# AD_1_V1_01.net
KiCad netlist of a schematic drawn in Altium Designer
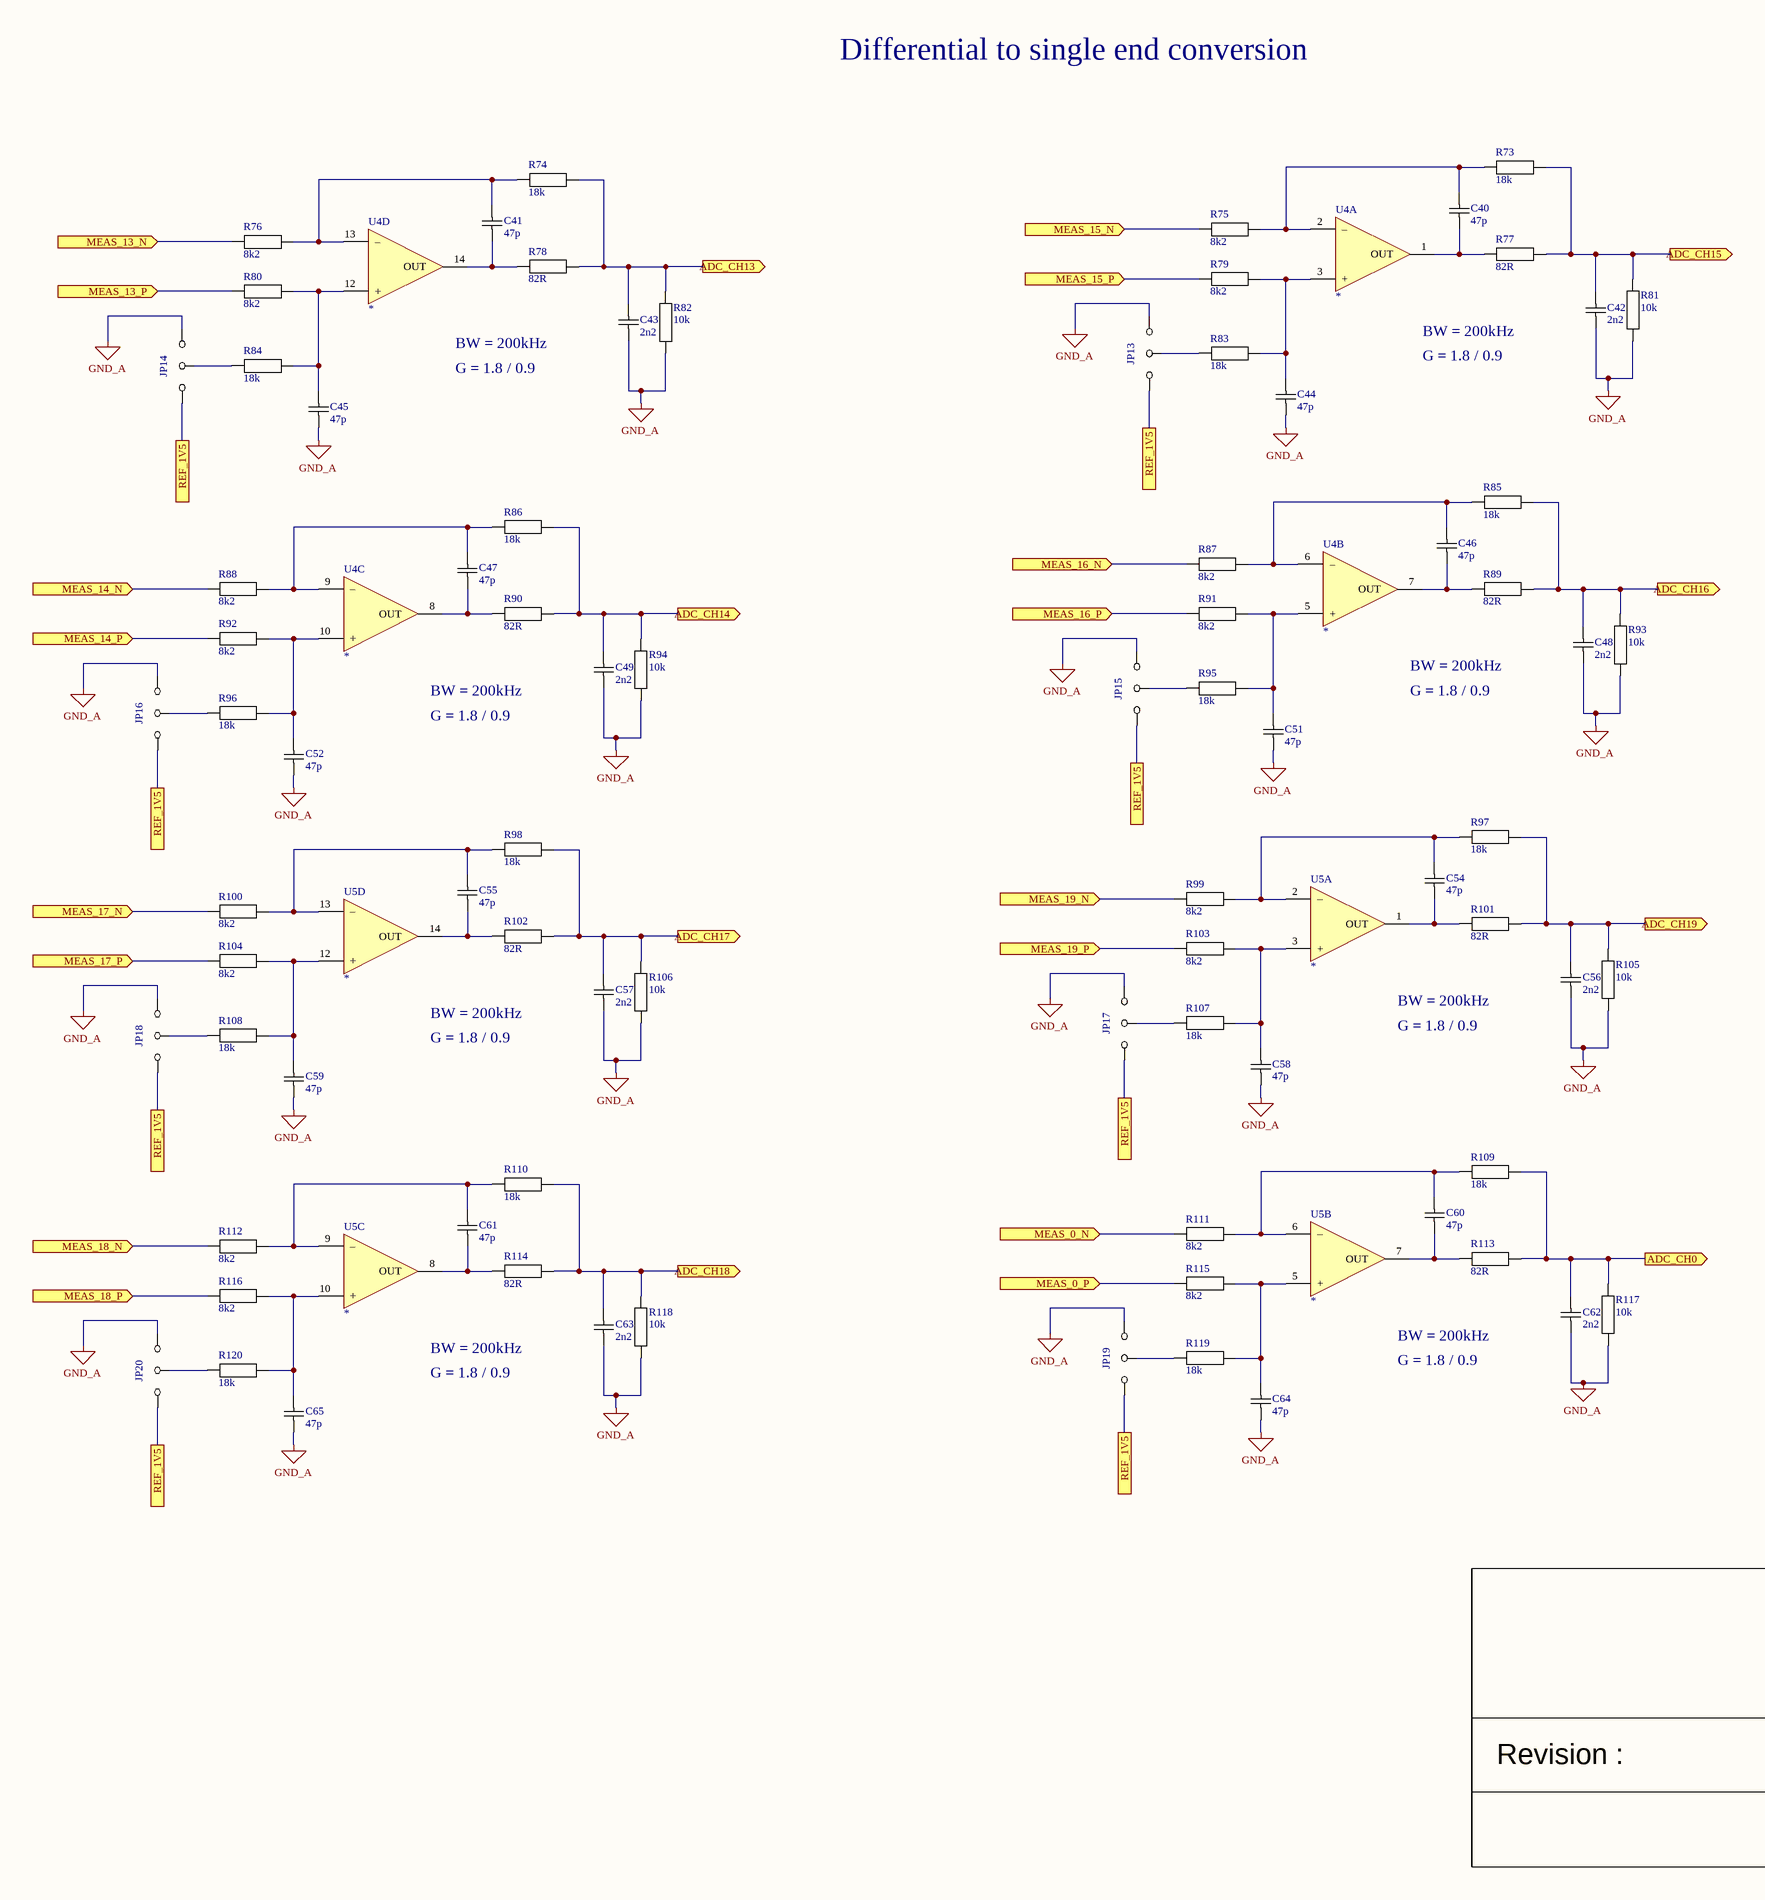
[diagram p0: AD_1_V1_01.SchDoc, left]
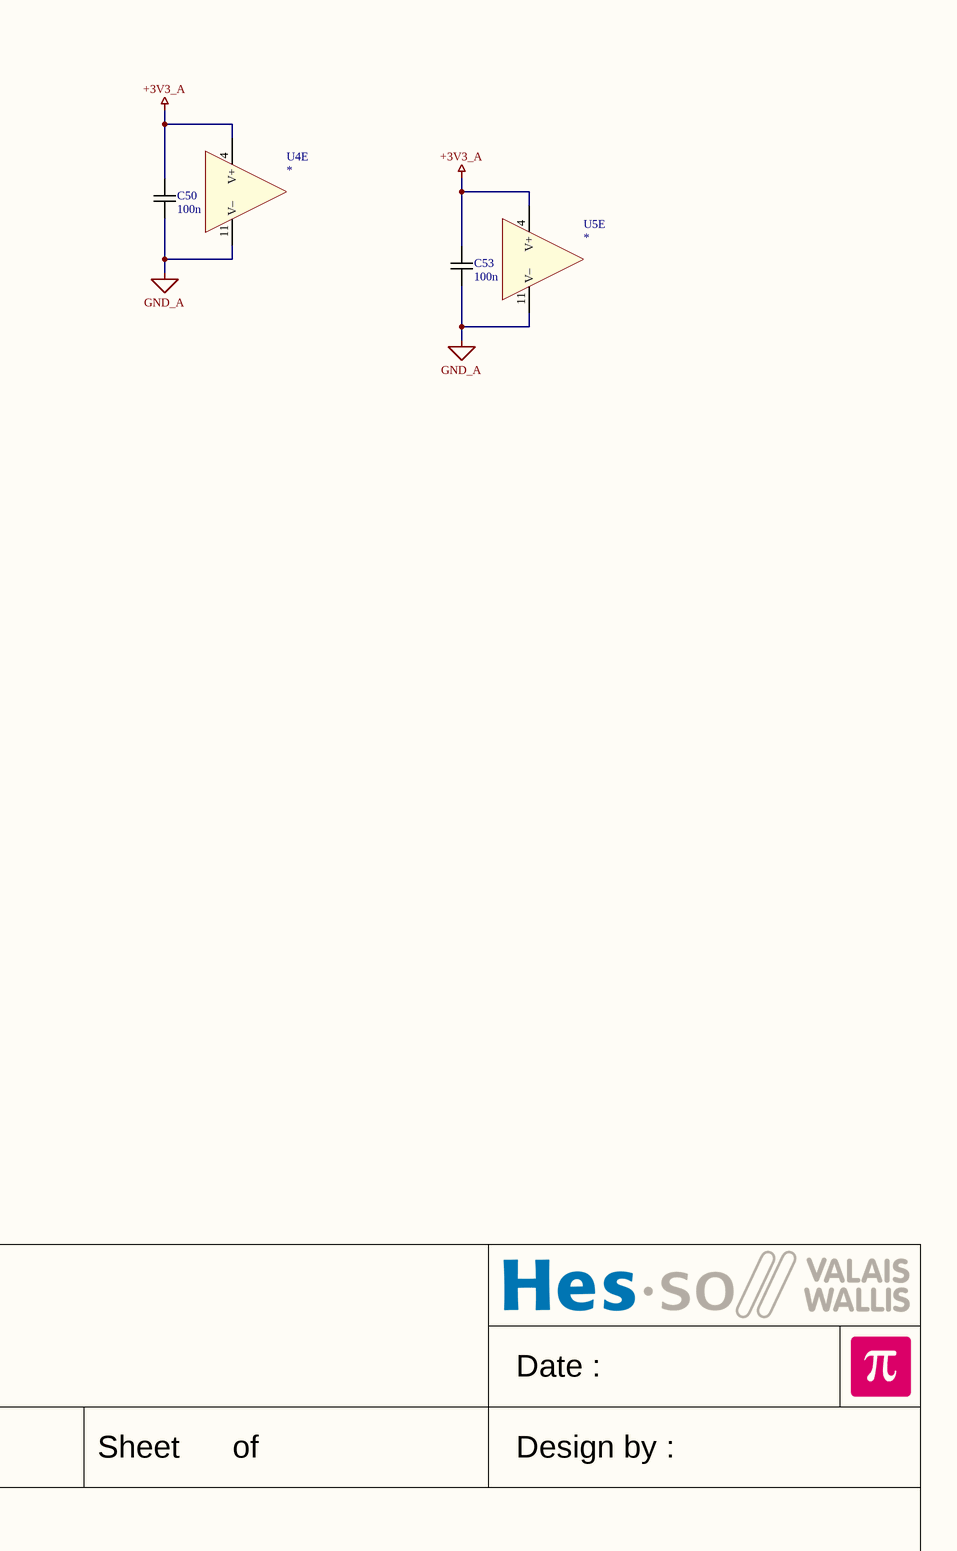
[diagram p1: AD_1_V1_01.SchDoc, right]

(export (version "E")
  (design (tool "Eeschema 10.0.6"))
  (components
    (comp (ref "C40")
      (value "47p")
      (footprint "CAPACITOR 1608 REFLOW")
      (description "Capacitor X7R 10% 50V 1608(0603)")
      (libsource (lib "Capacitor") (part "Capacitor"))
    )
    (comp (ref "C41")
      (value "47p")
      (footprint "CAPACITOR 1608 REFLOW")
      (description "Capacitor X7R 10% 50V 1608(0603)")
      (libsource (lib "Capacitor") (part "Capacitor"))
    )
    (comp (ref "C42")
      (value "2n2")
      (footprint "CAPACITOR 1608 REFLOW")
      (description "Capacitor X7R 10% 50V 1608(0603)")
      (libsource (lib "Capacitor") (part "Capacitor"))
    )
    (comp (ref "C43")
      (value "2n2")
      (footprint "CAPACITOR 1608 REFLOW")
      (description "Capacitor X7R 10% 50V 1608(0603)")
      (libsource (lib "Capacitor") (part "Capacitor"))
    )
    (comp (ref "C44")
      (value "47p")
      (footprint "CAPACITOR 1608 REFLOW")
      (description "Capacitor X7R 10% 50V 1608(0603)")
      (libsource (lib "Capacitor") (part "Capacitor"))
    )
    (comp (ref "C45")
      (value "47p")
      (footprint "CAPACITOR 1608 REFLOW")
      (description "Capacitor X7R 10% 50V 1608(0603)")
      (libsource (lib "Capacitor") (part "Capacitor"))
    )
    (comp (ref "C46")
      (value "47p")
      (footprint "CAPACITOR 1608 REFLOW")
      (description "Capacitor X7R 10% 50V 1608(0603)")
      (libsource (lib "Capacitor") (part "Capacitor"))
    )
    (comp (ref "C47")
      (value "47p")
      (footprint "CAPACITOR 1608 REFLOW")
      (description "Capacitor X7R 10% 50V 1608(0603)")
      (libsource (lib "Capacitor") (part "Capacitor"))
    )
    (comp (ref "C48")
      (value "2n2")
      (footprint "CAPACITOR 1608 REFLOW")
      (description "Capacitor X7R 10% 50V 1608(0603)")
      (libsource (lib "Capacitor") (part "Capacitor"))
    )
    (comp (ref "C49")
      (value "2n2")
      (footprint "CAPACITOR 1608 REFLOW")
      (description "Capacitor X7R 10% 50V 1608(0603)")
      (libsource (lib "Capacitor") (part "Capacitor"))
    )
    (comp (ref "C50")
      (value "100n")
      (footprint "CAPACITOR 1608 REFLOW")
      (description "Capacitor X7R 10% 50V 1608(0603)")
      (libsource (lib "Capacitor") (part "Capacitor"))
    )
    (comp (ref "C51")
      (value "47p")
      (footprint "CAPACITOR 1608 REFLOW")
      (description "Capacitor X7R 10% 50V 1608(0603)")
      (libsource (lib "Capacitor") (part "Capacitor"))
    )
    (comp (ref "C52")
      (value "47p")
      (footprint "CAPACITOR 1608 REFLOW")
      (description "Capacitor X7R 10% 50V 1608(0603)")
      (libsource (lib "Capacitor") (part "Capacitor"))
    )
    (comp (ref "C53")
      (value "100n")
      (footprint "CAPACITOR 1608 REFLOW")
      (description "Capacitor X7R 10% 50V 1608(0603)")
      (libsource (lib "Capacitor") (part "Capacitor"))
    )
    (comp (ref "C54")
      (value "47p")
      (footprint "CAPACITOR 1608 REFLOW")
      (description "Capacitor X7R 10% 50V 1608(0603)")
      (libsource (lib "Capacitor") (part "Capacitor"))
    )
    (comp (ref "C55")
      (value "47p")
      (footprint "CAPACITOR 1608 REFLOW")
      (description "Capacitor X7R 10% 50V 1608(0603)")
      (libsource (lib "Capacitor") (part "Capacitor"))
    )
    (comp (ref "C56")
      (value "2n2")
      (footprint "CAPACITOR 1608 REFLOW")
      (description "Capacitor X7R 10% 50V 1608(0603)")
      (libsource (lib "Capacitor") (part "Capacitor"))
    )
    (comp (ref "C57")
      (value "2n2")
      (footprint "CAPACITOR 1608 REFLOW")
      (description "Capacitor X7R 10% 50V 1608(0603)")
      (libsource (lib "Capacitor") (part "Capacitor"))
    )
    (comp (ref "C58")
      (value "47p")
      (footprint "CAPACITOR 1608 REFLOW")
      (description "Capacitor X7R 10% 50V 1608(0603)")
      (libsource (lib "Capacitor") (part "Capacitor"))
    )
    (comp (ref "C59")
      (value "47p")
      (footprint "CAPACITOR 1608 REFLOW")
      (description "Capacitor X7R 10% 50V 1608(0603)")
      (libsource (lib "Capacitor") (part "Capacitor"))
    )
    (comp (ref "C60")
      (value "47p")
      (footprint "CAPACITOR 1608 REFLOW")
      (description "Capacitor X7R 10% 50V 1608(0603)")
      (libsource (lib "Capacitor") (part "Capacitor"))
    )
    (comp (ref "C61")
      (value "47p")
      (footprint "CAPACITOR 1608 REFLOW")
      (description "Capacitor X7R 10% 50V 1608(0603)")
      (libsource (lib "Capacitor") (part "Capacitor"))
    )
    (comp (ref "C62")
      (value "2n2")
      (footprint "CAPACITOR 1608 REFLOW")
      (description "Capacitor X7R 10% 50V 1608(0603)")
      (libsource (lib "Capacitor") (part "Capacitor"))
    )
    (comp (ref "C63")
      (value "2n2")
      (footprint "CAPACITOR 1608 REFLOW")
      (description "Capacitor X7R 10% 50V 1608(0603)")
      (libsource (lib "Capacitor") (part "Capacitor"))
    )
    (comp (ref "C64")
      (value "47p")
      (footprint "CAPACITOR 1608 REFLOW")
      (description "Capacitor X7R 10% 50V 1608(0603)")
      (libsource (lib "Capacitor") (part "Capacitor"))
    )
    (comp (ref "C65")
      (value "47p")
      (footprint "CAPACITOR 1608 REFLOW")
      (description "Capacitor X7R 10% 50V 1608(0603)")
      (libsource (lib "Capacitor") (part "Capacitor"))
    )
    (comp (ref "JP13")
      (value "{Value}")
      (footprint "JUMPER3 SMD 1608")
      (description "JUMPER 3 POS")
      (libsource (lib "Jumper") (part "JUMPER 3 POS"))
    )
    (comp (ref "JP14")
      (value "{Value}")
      (footprint "JUMPER3 SMD 1608")
      (description "JUMPER 3 POS")
      (libsource (lib "Jumper") (part "JUMPER 3 POS"))
    )
    (comp (ref "JP15")
      (value "{Value}")
      (footprint "JUMPER3 SMD 1608")
      (description "JUMPER 3 POS")
      (libsource (lib "Jumper") (part "JUMPER 3 POS"))
    )
    (comp (ref "JP16")
      (value "{Value}")
      (footprint "JUMPER3 SMD 1608")
      (description "JUMPER 3 POS")
      (libsource (lib "Jumper") (part "JUMPER 3 POS"))
    )
    (comp (ref "JP17")
      (value "{Value}")
      (footprint "JUMPER3 SMD 1608")
      (description "JUMPER 3 POS")
      (libsource (lib "Jumper") (part "JUMPER 3 POS"))
    )
    (comp (ref "JP18")
      (value "{Value}")
      (footprint "JUMPER3 SMD 1608")
      (description "JUMPER 3 POS")
      (libsource (lib "Jumper") (part "JUMPER 3 POS"))
    )
    (comp (ref "JP19")
      (value "{Value}")
      (footprint "JUMPER3 SMD 1608")
      (description "JUMPER 3 POS")
      (libsource (lib "Jumper") (part "JUMPER 3 POS"))
    )
    (comp (ref "JP20")
      (value "{Value}")
      (footprint "JUMPER3 SMD 1608")
      (description "JUMPER 3 POS")
      (libsource (lib "Jumper") (part "JUMPER 3 POS"))
    )
    (comp (ref "R73")
      (value "18k")
      (footprint "RESISTOR 1608 REFLOW")
      (description "Resistor 1% 50V 100mW 1608(0603)")
      (libsource (lib "Resistor") (part "Resistor"))
    )
    (comp (ref "R74")
      (value "18k")
      (footprint "RESISTOR 1608 REFLOW")
      (description "Resistor 1% 50V 100mW 1608(0603)")
      (libsource (lib "Resistor") (part "Resistor"))
    )
    (comp (ref "R75")
      (value "8k2")
      (footprint "RESISTOR 1608 REFLOW")
      (description "Resistor 1% 50V 100mW 1608(0603)")
      (libsource (lib "Resistor") (part "Resistor"))
    )
    (comp (ref "R76")
      (value "8k2")
      (footprint "RESISTOR 1608 REFLOW")
      (description "Resistor 1% 50V 100mW 1608(0603)")
      (libsource (lib "Resistor") (part "Resistor"))
    )
    (comp (ref "R77")
      (value "82R")
      (footprint "RESISTOR 1608 REFLOW")
      (description "Resistor 1% 50V 100mW 1608(0603)")
      (libsource (lib "Resistor") (part "Resistor"))
    )
    (comp (ref "R78")
      (value "82R")
      (footprint "RESISTOR 1608 REFLOW")
      (description "Resistor 1% 50V 100mW 1608(0603)")
      (libsource (lib "Resistor") (part "Resistor"))
    )
    (comp (ref "R79")
      (value "8k2")
      (footprint "RESISTOR 1608 REFLOW")
      (description "Resistor 1% 50V 100mW 1608(0603)")
      (libsource (lib "Resistor") (part "Resistor"))
    )
    (comp (ref "R80")
      (value "8k2")
      (footprint "RESISTOR 1608 REFLOW")
      (description "Resistor 1% 50V 100mW 1608(0603)")
      (libsource (lib "Resistor") (part "Resistor"))
    )
    (comp (ref "R81")
      (value "10k")
      (footprint "RESISTOR 1608 REFLOW")
      (description "Resistor 1% 50V 100mW 1608(0603)")
      (libsource (lib "Resistor") (part "Resistor"))
    )
    (comp (ref "R82")
      (value "10k")
      (footprint "RESISTOR 1608 REFLOW")
      (description "Resistor 1% 50V 100mW 1608(0603)")
      (libsource (lib "Resistor") (part "Resistor"))
    )
    (comp (ref "R83")
      (value "18k")
      (footprint "RESISTOR 1608 REFLOW")
      (description "Resistor 1% 50V 100mW 1608(0603)")
      (libsource (lib "Resistor") (part "Resistor"))
    )
    (comp (ref "R84")
      (value "18k")
      (footprint "RESISTOR 1608 REFLOW")
      (description "Resistor 1% 50V 100mW 1608(0603)")
      (libsource (lib "Resistor") (part "Resistor"))
    )
    (comp (ref "R85")
      (value "18k")
      (footprint "RESISTOR 1608 REFLOW")
      (description "Resistor 1% 50V 100mW 1608(0603)")
      (libsource (lib "Resistor") (part "Resistor"))
    )
    (comp (ref "R86")
      (value "18k")
      (footprint "RESISTOR 1608 REFLOW")
      (description "Resistor 1% 50V 100mW 1608(0603)")
      (libsource (lib "Resistor") (part "Resistor"))
    )
    (comp (ref "R87")
      (value "8k2")
      (footprint "RESISTOR 1608 REFLOW")
      (description "Resistor 1% 50V 100mW 1608(0603)")
      (libsource (lib "Resistor") (part "Resistor"))
    )
    (comp (ref "R88")
      (value "8k2")
      (footprint "RESISTOR 1608 REFLOW")
      (description "Resistor 1% 50V 100mW 1608(0603)")
      (libsource (lib "Resistor") (part "Resistor"))
    )
    (comp (ref "R89")
      (value "82R")
      (footprint "RESISTOR 1608 REFLOW")
      (description "Resistor 1% 50V 100mW 1608(0603)")
      (libsource (lib "Resistor") (part "Resistor"))
    )
    (comp (ref "R90")
      (value "82R")
      (footprint "RESISTOR 1608 REFLOW")
      (description "Resistor 1% 50V 100mW 1608(0603)")
      (libsource (lib "Resistor") (part "Resistor"))
    )
    (comp (ref "R91")
      (value "8k2")
      (footprint "RESISTOR 1608 REFLOW")
      (description "Resistor 1% 50V 100mW 1608(0603)")
      (libsource (lib "Resistor") (part "Resistor"))
    )
    (comp (ref "R92")
      (value "8k2")
      (footprint "RESISTOR 1608 REFLOW")
      (description "Resistor 1% 50V 100mW 1608(0603)")
      (libsource (lib "Resistor") (part "Resistor"))
    )
    (comp (ref "R93")
      (value "10k")
      (footprint "RESISTOR 1608 REFLOW")
      (description "Resistor 1% 50V 100mW 1608(0603)")
      (libsource (lib "Resistor") (part "Resistor"))
    )
    (comp (ref "R94")
      (value "10k")
      (footprint "RESISTOR 1608 REFLOW")
      (description "Resistor 1% 50V 100mW 1608(0603)")
      (libsource (lib "Resistor") (part "Resistor"))
    )
    (comp (ref "R95")
      (value "18k")
      (footprint "RESISTOR 1608 REFLOW")
      (description "Resistor 1% 50V 100mW 1608(0603)")
      (libsource (lib "Resistor") (part "Resistor"))
    )
    (comp (ref "R96")
      (value "18k")
      (footprint "RESISTOR 1608 REFLOW")
      (description "Resistor 1% 50V 100mW 1608(0603)")
      (libsource (lib "Resistor") (part "Resistor"))
    )
    (comp (ref "R97")
      (value "18k")
      (footprint "RESISTOR 1608 REFLOW")
      (description "Resistor 1% 50V 100mW 1608(0603)")
      (libsource (lib "Resistor") (part "Resistor"))
    )
    (comp (ref "R98")
      (value "18k")
      (footprint "RESISTOR 1608 REFLOW")
      (description "Resistor 1% 50V 100mW 1608(0603)")
      (libsource (lib "Resistor") (part "Resistor"))
    )
    (comp (ref "R99")
      (value "8k2")
      (footprint "RESISTOR 1608 REFLOW")
      (description "Resistor 1% 50V 100mW 1608(0603)")
      (libsource (lib "Resistor") (part "Resistor"))
    )
    (comp (ref "R100")
      (value "8k2")
      (footprint "RESISTOR 1608 REFLOW")
      (description "Resistor 1% 50V 100mW 1608(0603)")
      (libsource (lib "Resistor") (part "Resistor"))
    )
    (comp (ref "R101")
      (value "82R")
      (footprint "RESISTOR 1608 REFLOW")
      (description "Resistor 1% 50V 100mW 1608(0603)")
      (libsource (lib "Resistor") (part "Resistor"))
    )
    (comp (ref "R102")
      (value "82R")
      (footprint "RESISTOR 1608 REFLOW")
      (description "Resistor 1% 50V 100mW 1608(0603)")
      (libsource (lib "Resistor") (part "Resistor"))
    )
    (comp (ref "R103")
      (value "8k2")
      (footprint "RESISTOR 1608 REFLOW")
      (description "Resistor 1% 50V 100mW 1608(0603)")
      (libsource (lib "Resistor") (part "Resistor"))
    )
    (comp (ref "R104")
      (value "8k2")
      (footprint "RESISTOR 1608 REFLOW")
      (description "Resistor 1% 50V 100mW 1608(0603)")
      (libsource (lib "Resistor") (part "Resistor"))
    )
    (comp (ref "R105")
      (value "10k")
      (footprint "RESISTOR 1608 REFLOW")
      (description "Resistor 1% 50V 100mW 1608(0603)")
      (libsource (lib "Resistor") (part "Resistor"))
    )
    (comp (ref "R106")
      (value "10k")
      (footprint "RESISTOR 1608 REFLOW")
      (description "Resistor 1% 50V 100mW 1608(0603)")
      (libsource (lib "Resistor") (part "Resistor"))
    )
    (comp (ref "R107")
      (value "18k")
      (footprint "RESISTOR 1608 REFLOW")
      (description "Resistor 1% 50V 100mW 1608(0603)")
      (libsource (lib "Resistor") (part "Resistor"))
    )
    (comp (ref "R108")
      (value "18k")
      (footprint "RESISTOR 1608 REFLOW")
      (description "Resistor 1% 50V 100mW 1608(0603)")
      (libsource (lib "Resistor") (part "Resistor"))
    )
    (comp (ref "R109")
      (value "18k")
      (footprint "RESISTOR 1608 REFLOW")
      (description "Resistor 1% 50V 100mW 1608(0603)")
      (libsource (lib "Resistor") (part "Resistor"))
    )
    (comp (ref "R110")
      (value "18k")
      (footprint "RESISTOR 1608 REFLOW")
      (description "Resistor 1% 50V 100mW 1608(0603)")
      (libsource (lib "Resistor") (part "Resistor"))
    )
    (comp (ref "R111")
      (value "8k2")
      (footprint "RESISTOR 1608 REFLOW")
      (description "Resistor 1% 50V 100mW 1608(0603)")
      (libsource (lib "Resistor") (part "Resistor"))
    )
    (comp (ref "R112")
      (value "8k2")
      (footprint "RESISTOR 1608 REFLOW")
      (description "Resistor 1% 50V 100mW 1608(0603)")
      (libsource (lib "Resistor") (part "Resistor"))
    )
    (comp (ref "R113")
      (value "82R")
      (footprint "RESISTOR 1608 REFLOW")
      (description "Resistor 1% 50V 100mW 1608(0603)")
      (libsource (lib "Resistor") (part "Resistor"))
    )
    (comp (ref "R114")
      (value "82R")
      (footprint "RESISTOR 1608 REFLOW")
      (description "Resistor 1% 50V 100mW 1608(0603)")
      (libsource (lib "Resistor") (part "Resistor"))
    )
    (comp (ref "R115")
      (value "8k2")
      (footprint "RESISTOR 1608 REFLOW")
      (description "Resistor 1% 50V 100mW 1608(0603)")
      (libsource (lib "Resistor") (part "Resistor"))
    )
    (comp (ref "R116")
      (value "8k2")
      (footprint "RESISTOR 1608 REFLOW")
      (description "Resistor 1% 50V 100mW 1608(0603)")
      (libsource (lib "Resistor") (part "Resistor"))
    )
    (comp (ref "R117")
      (value "10k")
      (footprint "RESISTOR 1608 REFLOW")
      (description "Resistor 1% 50V 100mW 1608(0603)")
      (libsource (lib "Resistor") (part "Resistor"))
    )
    (comp (ref "R118")
      (value "10k")
      (footprint "RESISTOR 1608 REFLOW")
      (description "Resistor 1% 50V 100mW 1608(0603)")
      (libsource (lib "Resistor") (part "Resistor"))
    )
    (comp (ref "R119")
      (value "18k")
      (footprint "RESISTOR 1608 REFLOW")
      (description "Resistor 1% 50V 100mW 1608(0603)")
      (libsource (lib "Resistor") (part "Resistor"))
    )
    (comp (ref "R120")
      (value "18k")
      (footprint "RESISTOR 1608 REFLOW")
      (description "Resistor 1% 50V 100mW 1608(0603)")
      (libsource (lib "Resistor") (part "Resistor"))
    )
    (comp (ref "U4")
      (value "*")
      (footprint "SO14 P1.27 C4.0X8.8 H1.75")
      (description "Generic quad OPA 14 pins")
      (libsource (lib "Amplifier") (part "OPA QUAD"))
    )
    (comp (ref "U5")
      (value "*")
      (footprint "SO14 P1.27 C4.0X8.8 H1.75")
      (description "Generic quad OPA 14 pins")
      (libsource (lib "Amplifier") (part "OPA QUAD"))
    )
  )
  (nets
    (net (code "1") (name "+3V3_A") (class "Default")
      (node (ref "C50") (pin "2") (pinfunction "2_2") (pintype "passive"))
      (node (ref "C53") (pin "2") (pinfunction "2_2") (pintype "passive"))
      (node (ref "U4") (pin "4") (pinfunction "V+_4") (pintype "passive"))
      (node (ref "U5") (pin "4") (pinfunction "V+_4") (pintype "passive"))
    )
    (net (code "2") (name "/ADC_CH0") (class "Default")
      (node (ref "C62") (pin "2") (pinfunction "2_2") (pintype "passive"))
      (node (ref "R109") (pin "2") (pinfunction "2_2") (pintype "passive"))
      (node (ref "R113") (pin "2") (pinfunction "2_2") (pintype "passive"))
      (node (ref "R117") (pin "1") (pinfunction "1_1") (pintype "passive"))
    )
    (net (code "3") (name "/ADC_CH13") (class "Default")
      (node (ref "C43") (pin "2") (pinfunction "2_2") (pintype "passive"))
      (node (ref "R74") (pin "2") (pinfunction "2_2") (pintype "passive"))
      (node (ref "R78") (pin "2") (pinfunction "2_2") (pintype "passive"))
      (node (ref "R82") (pin "1") (pinfunction "1_1") (pintype "passive"))
    )
    (net (code "4") (name "/ADC_CH14") (class "Default")
      (node (ref "C49") (pin "2") (pinfunction "2_2") (pintype "passive"))
      (node (ref "R86") (pin "2") (pinfunction "2_2") (pintype "passive"))
      (node (ref "R90") (pin "2") (pinfunction "2_2") (pintype "passive"))
      (node (ref "R94") (pin "1") (pinfunction "1_1") (pintype "passive"))
    )
    (net (code "5") (name "/ADC_CH15") (class "Default")
      (node (ref "C42") (pin "2") (pinfunction "2_2") (pintype "passive"))
      (node (ref "R73") (pin "2") (pinfunction "2_2") (pintype "passive"))
      (node (ref "R77") (pin "2") (pinfunction "2_2") (pintype "passive"))
      (node (ref "R81") (pin "1") (pinfunction "1_1") (pintype "passive"))
    )
    (net (code "6") (name "/ADC_CH16") (class "Default")
      (node (ref "C48") (pin "2") (pinfunction "2_2") (pintype "passive"))
      (node (ref "R85") (pin "2") (pinfunction "2_2") (pintype "passive"))
      (node (ref "R89") (pin "2") (pinfunction "2_2") (pintype "passive"))
      (node (ref "R93") (pin "1") (pinfunction "1_1") (pintype "passive"))
    )
    (net (code "7") (name "/ADC_CH17") (class "Default")
      (node (ref "C57") (pin "2") (pinfunction "2_2") (pintype "passive"))
      (node (ref "R102") (pin "2") (pinfunction "2_2") (pintype "passive"))
      (node (ref "R106") (pin "1") (pinfunction "1_1") (pintype "passive"))
      (node (ref "R98") (pin "2") (pinfunction "2_2") (pintype "passive"))
    )
    (net (code "8") (name "/ADC_CH18") (class "Default")
      (node (ref "C63") (pin "2") (pinfunction "2_2") (pintype "passive"))
      (node (ref "R110") (pin "2") (pinfunction "2_2") (pintype "passive"))
      (node (ref "R114") (pin "2") (pinfunction "2_2") (pintype "passive"))
      (node (ref "R118") (pin "1") (pinfunction "1_1") (pintype "passive"))
    )
    (net (code "9") (name "/ADC_CH19") (class "Default")
      (node (ref "C56") (pin "2") (pinfunction "2_2") (pintype "passive"))
      (node (ref "R101") (pin "2") (pinfunction "2_2") (pintype "passive"))
      (node (ref "R105") (pin "1") (pinfunction "1_1") (pintype "passive"))
      (node (ref "R97") (pin "2") (pinfunction "2_2") (pintype "passive"))
    )
    (net (code "10") (name "/MEAS_0_N") (class "Default")
      (node (ref "R111") (pin "1") (pinfunction "1_1") (pintype "passive"))
    )
    (net (code "11") (name "/MEAS_0_P") (class "Default")
      (node (ref "R115") (pin "1") (pinfunction "1_1") (pintype "passive"))
    )
    (net (code "12") (name "/MEAS_13_N") (class "Default")
      (node (ref "R76") (pin "1") (pinfunction "1_1") (pintype "passive"))
    )
    (net (code "13") (name "/MEAS_13_P") (class "Default")
      (node (ref "R80") (pin "1") (pinfunction "1_1") (pintype "passive"))
    )
    (net (code "14") (name "/MEAS_14_N") (class "Default")
      (node (ref "R88") (pin "1") (pinfunction "1_1") (pintype "passive"))
    )
    (net (code "15") (name "/MEAS_14_P") (class "Default")
      (node (ref "R92") (pin "1") (pinfunction "1_1") (pintype "passive"))
    )
    (net (code "16") (name "/MEAS_15_N") (class "Default")
      (node (ref "R75") (pin "1") (pinfunction "1_1") (pintype "passive"))
    )
    (net (code "17") (name "/MEAS_15_P") (class "Default")
      (node (ref "R79") (pin "1") (pinfunction "1_1") (pintype "passive"))
    )
    (net (code "18") (name "/MEAS_16_N") (class "Default")
      (node (ref "R87") (pin "1") (pinfunction "1_1") (pintype "passive"))
    )
    (net (code "19") (name "/MEAS_16_P") (class "Default")
      (node (ref "R91") (pin "1") (pinfunction "1_1") (pintype "passive"))
    )
    (net (code "20") (name "/MEAS_17_N") (class "Default")
      (node (ref "R100") (pin "1") (pinfunction "1_1") (pintype "passive"))
    )
    (net (code "21") (name "/MEAS_17_P") (class "Default")
      (node (ref "R104") (pin "1") (pinfunction "1_1") (pintype "passive"))
    )
    (net (code "22") (name "/MEAS_18_N") (class "Default")
      (node (ref "R112") (pin "1") (pinfunction "1_1") (pintype "passive"))
    )
    (net (code "23") (name "/MEAS_18_P") (class "Default")
      (node (ref "R116") (pin "1") (pinfunction "1_1") (pintype "passive"))
    )
    (net (code "24") (name "/MEAS_19_N") (class "Default")
      (node (ref "R99") (pin "1") (pinfunction "1_1") (pintype "passive"))
    )
    (net (code "25") (name "/MEAS_19_P") (class "Default")
      (node (ref "R103") (pin "1") (pinfunction "1_1") (pintype "passive"))
    )
    (net (code "26") (name "/REF_1V5") (class "Default")
      (node (ref "JP13") (pin "1") (pinfunction "1_1") (pintype "passive"))
      (node (ref "JP14") (pin "1") (pinfunction "1_1") (pintype "passive"))
      (node (ref "JP15") (pin "1") (pinfunction "1_1") (pintype "passive"))
      (node (ref "JP16") (pin "1") (pinfunction "1_1") (pintype "passive"))
      (node (ref "JP17") (pin "1") (pinfunction "1_1") (pintype "passive"))
      (node (ref "JP18") (pin "1") (pinfunction "1_1") (pintype "passive"))
      (node (ref "JP19") (pin "1") (pinfunction "1_1") (pintype "passive"))
      (node (ref "JP20") (pin "1") (pinfunction "1_1") (pintype "passive"))
    )
    (net (code "27") (name "GND_A") (class "Default")
      (node (ref "C42") (pin "1") (pinfunction "1_1") (pintype "passive"))
      (node (ref "C43") (pin "1") (pinfunction "1_1") (pintype "passive"))
      (node (ref "C44") (pin "1") (pinfunction "1_1") (pintype "passive"))
      (node (ref "C45") (pin "1") (pinfunction "1_1") (pintype "passive"))
      (node (ref "C48") (pin "1") (pinfunction "1_1") (pintype "passive"))
      (node (ref "C49") (pin "1") (pinfunction "1_1") (pintype "passive"))
      (node (ref "C50") (pin "1") (pinfunction "1_1") (pintype "passive"))
      (node (ref "C51") (pin "1") (pinfunction "1_1") (pintype "passive"))
      (node (ref "C52") (pin "1") (pinfunction "1_1") (pintype "passive"))
      (node (ref "C53") (pin "1") (pinfunction "1_1") (pintype "passive"))
      (node (ref "C56") (pin "1") (pinfunction "1_1") (pintype "passive"))
      (node (ref "C57") (pin "1") (pinfunction "1_1") (pintype "passive"))
      (node (ref "C58") (pin "1") (pinfunction "1_1") (pintype "passive"))
      (node (ref "C59") (pin "1") (pinfunction "1_1") (pintype "passive"))
      (node (ref "C62") (pin "1") (pinfunction "1_1") (pintype "passive"))
      (node (ref "C63") (pin "1") (pinfunction "1_1") (pintype "passive"))
      (node (ref "C64") (pin "1") (pinfunction "1_1") (pintype "passive"))
      (node (ref "C65") (pin "1") (pinfunction "1_1") (pintype "passive"))
      (node (ref "JP13") (pin "3") (pinfunction "3_3") (pintype "passive"))
      (node (ref "JP14") (pin "3") (pinfunction "3_3") (pintype "passive"))
      (node (ref "JP15") (pin "3") (pinfunction "3_3") (pintype "passive"))
      (node (ref "JP16") (pin "3") (pinfunction "3_3") (pintype "passive"))
      (node (ref "JP17") (pin "3") (pinfunction "3_3") (pintype "passive"))
      (node (ref "JP18") (pin "3") (pinfunction "3_3") (pintype "passive"))
      (node (ref "JP19") (pin "3") (pinfunction "3_3") (pintype "passive"))
      (node (ref "JP20") (pin "3") (pinfunction "3_3") (pintype "passive"))
      (node (ref "R105") (pin "2") (pinfunction "2_2") (pintype "passive"))
      (node (ref "R106") (pin "2") (pinfunction "2_2") (pintype "passive"))
      (node (ref "R117") (pin "2") (pinfunction "2_2") (pintype "passive"))
      (node (ref "R118") (pin "2") (pinfunction "2_2") (pintype "passive"))
      (node (ref "R81") (pin "2") (pinfunction "2_2") (pintype "passive"))
      (node (ref "R82") (pin "2") (pinfunction "2_2") (pintype "passive"))
      (node (ref "R93") (pin "2") (pinfunction "2_2") (pintype "passive"))
      (node (ref "R94") (pin "2") (pinfunction "2_2") (pintype "passive"))
      (node (ref "U4") (pin "11") (pinfunction "V–_11") (pintype "passive"))
      (node (ref "U5") (pin "11") (pinfunction "V–_11") (pintype "passive"))
    )
    (net (code "28") (name "Net-(JP13-Pad2)") (class "Default")
      (node (ref "JP13") (pin "2") (pinfunction "2_2") (pintype "passive"))
      (node (ref "R83") (pin "2") (pinfunction "2_2") (pintype "passive"))
    )
    (net (code "29") (name "Net-(JP14-Pad2)") (class "Default")
      (node (ref "JP14") (pin "2") (pinfunction "2_2") (pintype "passive"))
      (node (ref "R84") (pin "2") (pinfunction "2_2") (pintype "passive"))
    )
    (net (code "30") (name "Net-(JP15-Pad2)") (class "Default")
      (node (ref "JP15") (pin "2") (pinfunction "2_2") (pintype "passive"))
      (node (ref "R95") (pin "2") (pinfunction "2_2") (pintype "passive"))
    )
    (net (code "31") (name "Net-(JP16-Pad2)") (class "Default")
      (node (ref "JP16") (pin "2") (pinfunction "2_2") (pintype "passive"))
      (node (ref "R96") (pin "2") (pinfunction "2_2") (pintype "passive"))
    )
    (net (code "32") (name "Net-(JP17-Pad2)") (class "Default")
      (node (ref "JP17") (pin "2") (pinfunction "2_2") (pintype "passive"))
      (node (ref "R107") (pin "2") (pinfunction "2_2") (pintype "passive"))
    )
    (net (code "33") (name "Net-(JP18-Pad2)") (class "Default")
      (node (ref "JP18") (pin "2") (pinfunction "2_2") (pintype "passive"))
      (node (ref "R108") (pin "2") (pinfunction "2_2") (pintype "passive"))
    )
    (net (code "34") (name "Net-(JP19-Pad2)") (class "Default")
      (node (ref "JP19") (pin "2") (pinfunction "2_2") (pintype "passive"))
      (node (ref "R119") (pin "2") (pinfunction "2_2") (pintype "passive"))
    )
    (net (code "35") (name "Net-(JP20-Pad2)") (class "Default")
      (node (ref "JP20") (pin "2") (pinfunction "2_2") (pintype "passive"))
      (node (ref "R120") (pin "2") (pinfunction "2_2") (pintype "passive"))
    )
    (net (code "36") (name "Net-(U4A-+)") (class "Default")
      (node (ref "C44") (pin "2") (pinfunction "2_2") (pintype "passive"))
      (node (ref "R79") (pin "2") (pinfunction "2_2") (pintype "passive"))
      (node (ref "R83") (pin "1") (pinfunction "1_1") (pintype "passive"))
      (node (ref "U4") (pin "3") (pinfunction "+_3") (pintype "passive"))
    )
    (net (code "37") (name "Net-(U4A-OUT)") (class "Default")
      (node (ref "C40") (pin "1") (pinfunction "1_1") (pintype "passive"))
      (node (ref "R77") (pin "1") (pinfunction "1_1") (pintype "passive"))
      (node (ref "U4") (pin "1") (pinfunction "OUT_1") (pintype "passive"))
    )
    (net (code "38") (name "Net-(U4A-–)") (class "Default")
      (node (ref "C40") (pin "2") (pinfunction "2_2") (pintype "passive"))
      (node (ref "R73") (pin "1") (pinfunction "1_1") (pintype "passive"))
      (node (ref "R75") (pin "2") (pinfunction "2_2") (pintype "passive"))
      (node (ref "U4") (pin "2") (pinfunction "–_2") (pintype "passive"))
    )
    (net (code "39") (name "Net-(U4B-+)") (class "Default")
      (node (ref "C51") (pin "2") (pinfunction "2_2") (pintype "passive"))
      (node (ref "R91") (pin "2") (pinfunction "2_2") (pintype "passive"))
      (node (ref "R95") (pin "1") (pinfunction "1_1") (pintype "passive"))
      (node (ref "U4") (pin "5") (pinfunction "+_5") (pintype "passive"))
    )
    (net (code "40") (name "Net-(U4B-OUT)") (class "Default")
      (node (ref "C46") (pin "1") (pinfunction "1_1") (pintype "passive"))
      (node (ref "R89") (pin "1") (pinfunction "1_1") (pintype "passive"))
      (node (ref "U4") (pin "7") (pinfunction "OUT_7") (pintype "passive"))
    )
    (net (code "41") (name "Net-(U4B-–)") (class "Default")
      (node (ref "C46") (pin "2") (pinfunction "2_2") (pintype "passive"))
      (node (ref "R85") (pin "1") (pinfunction "1_1") (pintype "passive"))
      (node (ref "R87") (pin "2") (pinfunction "2_2") (pintype "passive"))
      (node (ref "U4") (pin "6") (pinfunction "–_6") (pintype "passive"))
    )
    (net (code "42") (name "Net-(U4C-+)") (class "Default")
      (node (ref "C52") (pin "2") (pinfunction "2_2") (pintype "passive"))
      (node (ref "R92") (pin "2") (pinfunction "2_2") (pintype "passive"))
      (node (ref "R96") (pin "1") (pinfunction "1_1") (pintype "passive"))
      (node (ref "U4") (pin "10") (pinfunction "+_10") (pintype "passive"))
    )
    (net (code "43") (name "Net-(U4C-OUT)") (class "Default")
      (node (ref "C47") (pin "1") (pinfunction "1_1") (pintype "passive"))
      (node (ref "R90") (pin "1") (pinfunction "1_1") (pintype "passive"))
      (node (ref "U4") (pin "8") (pinfunction "OUT_8") (pintype "passive"))
    )
    (net (code "44") (name "Net-(U4C-–)") (class "Default")
      (node (ref "C47") (pin "2") (pinfunction "2_2") (pintype "passive"))
      (node (ref "R86") (pin "1") (pinfunction "1_1") (pintype "passive"))
      (node (ref "R88") (pin "2") (pinfunction "2_2") (pintype "passive"))
      (node (ref "U4") (pin "9") (pinfunction "–_9") (pintype "passive"))
    )
    (net (code "45") (name "Net-(U4D-+)") (class "Default")
      (node (ref "C45") (pin "2") (pinfunction "2_2") (pintype "passive"))
      (node (ref "R80") (pin "2") (pinfunction "2_2") (pintype "passive"))
      (node (ref "R84") (pin "1") (pinfunction "1_1") (pintype "passive"))
      (node (ref "U4") (pin "12") (pinfunction "+_12") (pintype "passive"))
    )
    (net (code "46") (name "Net-(U4D-OUT)") (class "Default")
      (node (ref "C41") (pin "1") (pinfunction "1_1") (pintype "passive"))
      (node (ref "R78") (pin "1") (pinfunction "1_1") (pintype "passive"))
      (node (ref "U4") (pin "14") (pinfunction "OUT_14") (pintype "passive"))
    )
    (net (code "47") (name "Net-(U4D-–)") (class "Default")
      (node (ref "C41") (pin "2") (pinfunction "2_2") (pintype "passive"))
      (node (ref "R74") (pin "1") (pinfunction "1_1") (pintype "passive"))
      (node (ref "R76") (pin "2") (pinfunction "2_2") (pintype "passive"))
      (node (ref "U4") (pin "13") (pinfunction "–_13") (pintype "passive"))
    )
    (net (code "48") (name "Net-(U5A-+)") (class "Default")
      (node (ref "C58") (pin "2") (pinfunction "2_2") (pintype "passive"))
      (node (ref "R103") (pin "2") (pinfunction "2_2") (pintype "passive"))
      (node (ref "R107") (pin "1") (pinfunction "1_1") (pintype "passive"))
      (node (ref "U5") (pin "3") (pinfunction "+_3") (pintype "passive"))
    )
    (net (code "49") (name "Net-(U5A-OUT)") (class "Default")
      (node (ref "C54") (pin "1") (pinfunction "1_1") (pintype "passive"))
      (node (ref "R101") (pin "1") (pinfunction "1_1") (pintype "passive"))
      (node (ref "U5") (pin "1") (pinfunction "OUT_1") (pintype "passive"))
    )
    (net (code "50") (name "Net-(U5A-–)") (class "Default")
      (node (ref "C54") (pin "2") (pinfunction "2_2") (pintype "passive"))
      (node (ref "R97") (pin "1") (pinfunction "1_1") (pintype "passive"))
      (node (ref "R99") (pin "2") (pinfunction "2_2") (pintype "passive"))
      (node (ref "U5") (pin "2") (pinfunction "–_2") (pintype "passive"))
    )
    (net (code "51") (name "Net-(U5B-+)") (class "Default")
      (node (ref "C64") (pin "2") (pinfunction "2_2") (pintype "passive"))
      (node (ref "R115") (pin "2") (pinfunction "2_2") (pintype "passive"))
      (node (ref "R119") (pin "1") (pinfunction "1_1") (pintype "passive"))
      (node (ref "U5") (pin "5") (pinfunction "+_5") (pintype "passive"))
    )
    (net (code "52") (name "Net-(U5B-OUT)") (class "Default")
      (node (ref "C60") (pin "1") (pinfunction "1_1") (pintype "passive"))
      (node (ref "R113") (pin "1") (pinfunction "1_1") (pintype "passive"))
      (node (ref "U5") (pin "7") (pinfunction "OUT_7") (pintype "passive"))
    )
    (net (code "53") (name "Net-(U5B-–)") (class "Default")
      (node (ref "C60") (pin "2") (pinfunction "2_2") (pintype "passive"))
      (node (ref "R109") (pin "1") (pinfunction "1_1") (pintype "passive"))
      (node (ref "R111") (pin "2") (pinfunction "2_2") (pintype "passive"))
      (node (ref "U5") (pin "6") (pinfunction "–_6") (pintype "passive"))
    )
    (net (code "54") (name "Net-(U5C-+)") (class "Default")
      (node (ref "C65") (pin "2") (pinfunction "2_2") (pintype "passive"))
      (node (ref "R116") (pin "2") (pinfunction "2_2") (pintype "passive"))
      (node (ref "R120") (pin "1") (pinfunction "1_1") (pintype "passive"))
      (node (ref "U5") (pin "10") (pinfunction "+_10") (pintype "passive"))
    )
    (net (code "55") (name "Net-(U5C-OUT)") (class "Default")
      (node (ref "C61") (pin "1") (pinfunction "1_1") (pintype "passive"))
      (node (ref "R114") (pin "1") (pinfunction "1_1") (pintype "passive"))
      (node (ref "U5") (pin "8") (pinfunction "OUT_8") (pintype "passive"))
    )
    (net (code "56") (name "Net-(U5C-–)") (class "Default")
      (node (ref "C61") (pin "2") (pinfunction "2_2") (pintype "passive"))
      (node (ref "R110") (pin "1") (pinfunction "1_1") (pintype "passive"))
      (node (ref "R112") (pin "2") (pinfunction "2_2") (pintype "passive"))
      (node (ref "U5") (pin "9") (pinfunction "–_9") (pintype "passive"))
    )
    (net (code "57") (name "Net-(U5D-+)") (class "Default")
      (node (ref "C59") (pin "2") (pinfunction "2_2") (pintype "passive"))
      (node (ref "R104") (pin "2") (pinfunction "2_2") (pintype "passive"))
      (node (ref "R108") (pin "1") (pinfunction "1_1") (pintype "passive"))
      (node (ref "U5") (pin "12") (pinfunction "+_12") (pintype "passive"))
    )
    (net (code "58") (name "Net-(U5D-OUT)") (class "Default")
      (node (ref "C55") (pin "1") (pinfunction "1_1") (pintype "passive"))
      (node (ref "R102") (pin "1") (pinfunction "1_1") (pintype "passive"))
      (node (ref "U5") (pin "14") (pinfunction "OUT_14") (pintype "passive"))
    )
    (net (code "59") (name "Net-(U5D-–)") (class "Default")
      (node (ref "C55") (pin "2") (pinfunction "2_2") (pintype "passive"))
      (node (ref "R100") (pin "2") (pinfunction "2_2") (pintype "passive"))
      (node (ref "R98") (pin "1") (pinfunction "1_1") (pintype "passive"))
      (node (ref "U5") (pin "13") (pinfunction "–_13") (pintype "passive"))
    )
  )
)
